# FBB_Sch.net
KiCad netlist of a schematic drawn in Altium Designer
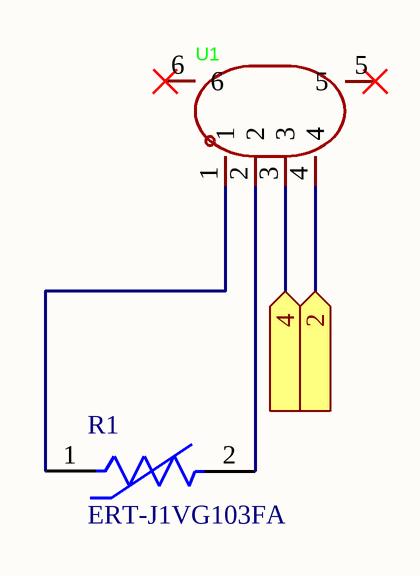
[diagram p0: FBB_Sch.SchDoc]

(export (version "E")
  (design (tool "Eeschema 10.0.6"))
  (components
    (comp (ref "R1")
      (value "ERT-J1VG103FA")
      (footprint "FP-ERTJ1-MFG")
      (description "THERMISTOR NTC 10KOHM 3380K 0603")
      (fields (field (name "TOLERANCE") "1%"))
      (libsource (lib "Altium Content Vault") (part "3b148a6ebabc5fb4d708a66c052d352"))
    )
    (comp (ref "U1")
      (value "WAFER-MX1.25-4PWB")
      (footprint "CONN-SMD_4P-P1.25_WAFER-MX1.25-4PWB")
      (fields (field (name "MANUFACTURER") "XUNPU(讯普)"))
      (libsource (lib "Zixi's  personal space") (part "WAFER-MX1.25-4PWB"))
    )
  )
  (nets
    (net (code "1") (name "/2") (class "Default")
      (node (ref "U1") (pin "4") (pinfunction "4_4") (pintype "passive"))
    )
    (net (code "2") (name "/4") (class "Default")
      (node (ref "U1") (pin "3") (pinfunction "3_3") (pintype "passive"))
    )
    (net (code "3") (name "Net-(R1-Pad1)") (class "Default")
      (node (ref "R1") (pin "1") (pinfunction "1_1") (pintype "passive"))
      (node (ref "U1") (pin "1") (pinfunction "1_1") (pintype "passive"))
    )
    (net (code "4") (name "Net-(R1-Pad2)") (class "Default")
      (node (ref "R1") (pin "2") (pinfunction "2_2") (pintype "passive"))
      (node (ref "U1") (pin "2") (pinfunction "2_2") (pintype "passive"))
    )
    (net (code "5") (name "unconnected-(U1-Pad5)") (class "Default")
      (node (ref "U1") (pin "5") (pinfunction "5_5") (pintype "passive+no_connect"))
    )
    (net (code "6") (name "unconnected-(U1-Pad6)") (class "Default")
      (node (ref "U1") (pin "6") (pinfunction "6_6") (pintype "passive+no_connect"))
    )
  )
)
